# Teensy_3_1_XBee_Adapter.net
KiCad netlist of a schematic drawn in EAGLE
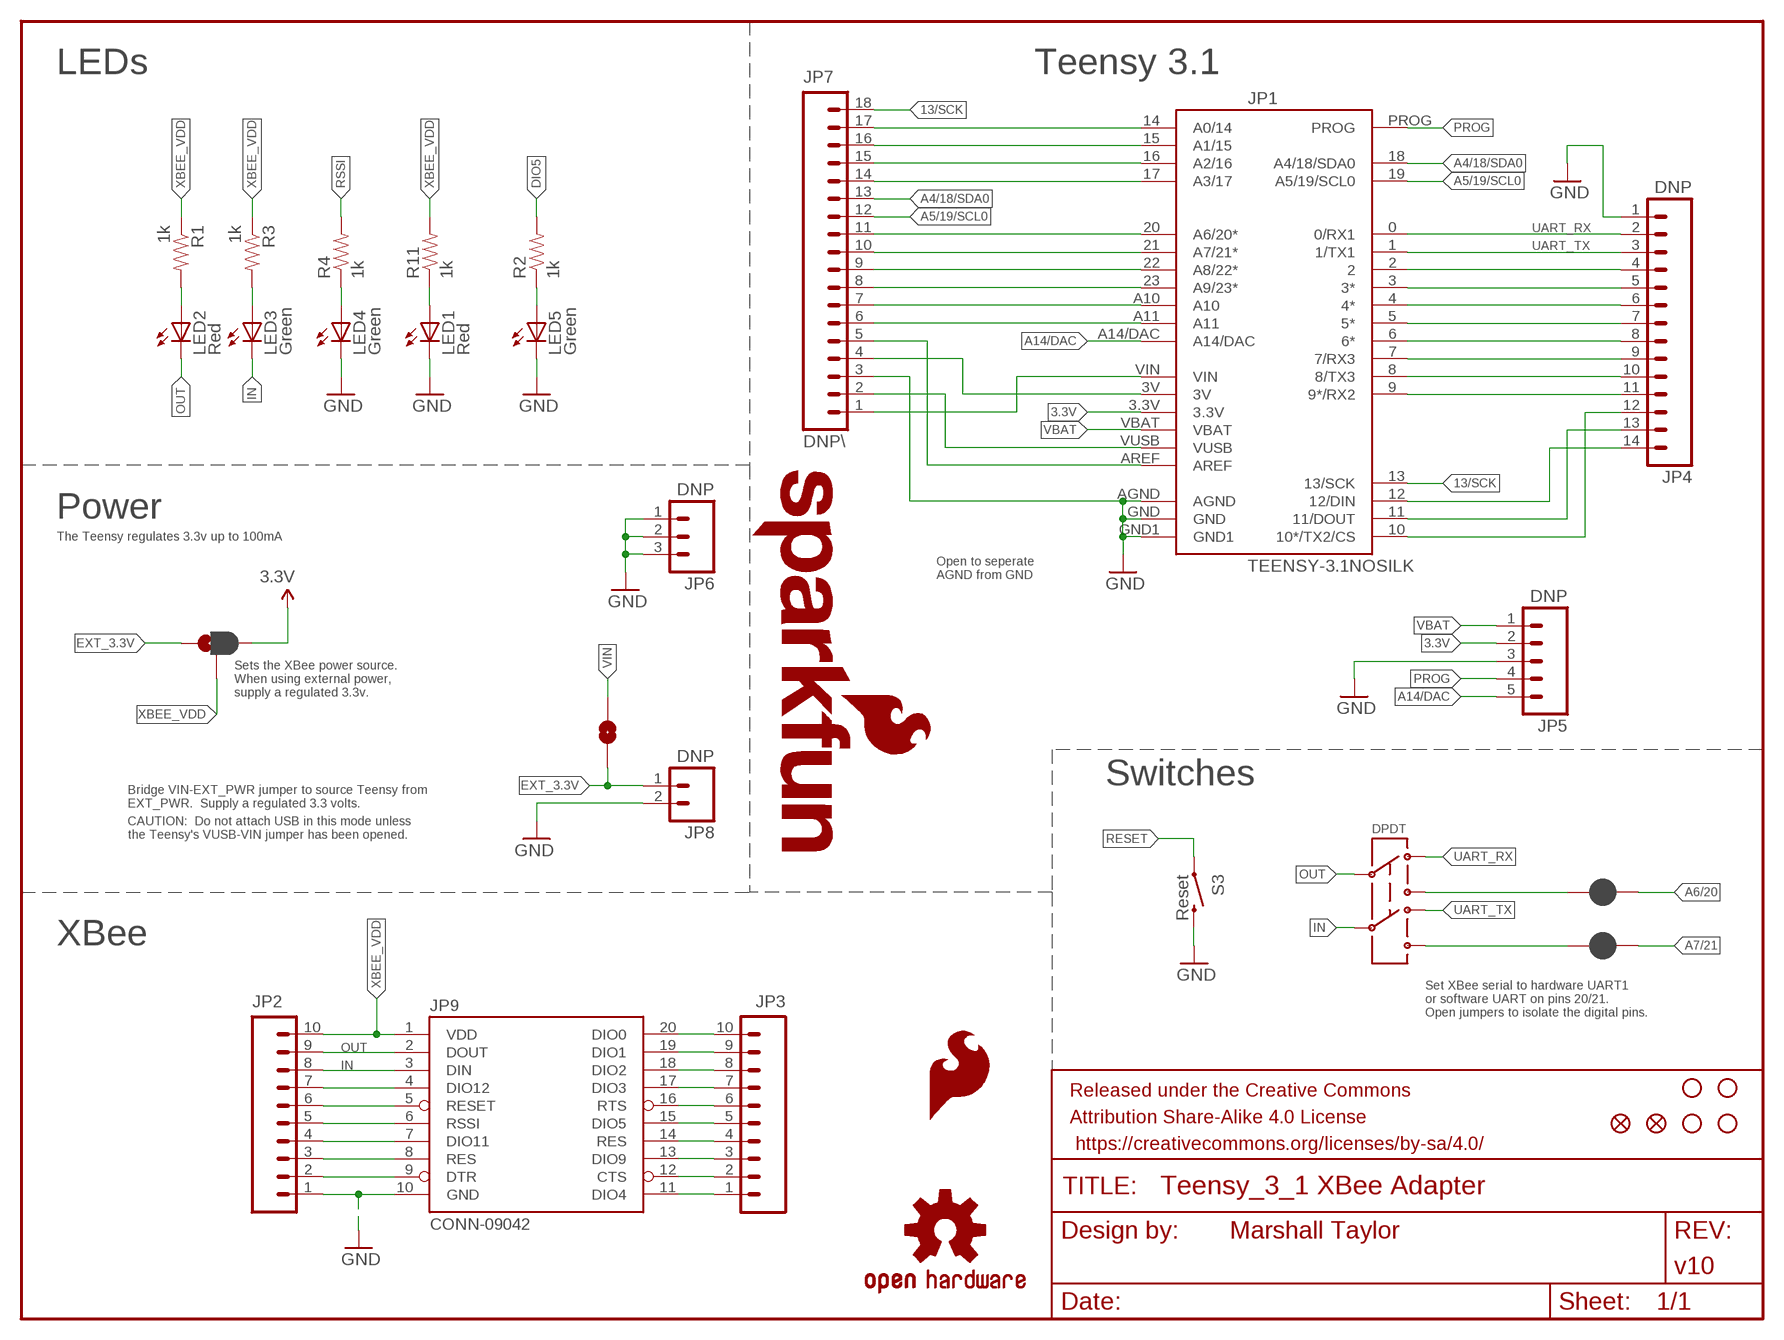
[diagram p0: schematic, sheet 1]

(export (version "E")
  (design (tool "Eeschema 10.0.6"))
  (components
    (comp (ref "FID1")
      (value "FIDUCIAL1X2")
      (footprint "eagle-import:FIDUCIAL-1X2")
      (libsource (lib "eagle-import") (part "FIDUCIAL1X2"))
    )
    (comp (ref "FID2")
      (value "FIDUCIAL1X2")
      (footprint "eagle-import:FIDUCIAL-1X2")
      (libsource (lib "eagle-import") (part "FIDUCIAL1X2"))
    )
    (comp (ref "FRAME1")
      (value "FRAME-LETTER")
      (footprint "eagle-import:CREATIVE_COMMONS")
      (fields
        (field (name "DESIGNER") "Marshall Taylor")
        (field (name "VERSION") "v10")
        (field (name "DESIGNER_1") "Marshall Taylor")
        (field (name "VERSION_1") "v10")
      )
      (libsource (lib "eagle-import") (part "FRAME-LETTER"))
    )
    (comp (ref "JP1")
      (value "TEENSY-3.1NOSILK")
      (footprint "eagle-import:TEENSY-3.1_NOSILK")
      (libsource (lib "eagle-import") (part "TEENSY-3.1NOSILK"))
    )
    (comp (ref "JP2")
      (value "M10NO_SILK_PTH_FEMALE")
      (footprint "eagle-import:1X10_NO_SILK")
      (libsource (lib "eagle-import") (part "M10NO_SILK_PTH_FEMALE"))
    )
    (comp (ref "JP3")
      (value "M10NO_SILK_PTH_FEMALE")
      (footprint "eagle-import:1X10_NO_SILK")
      (libsource (lib "eagle-import") (part "M10NO_SILK_PTH_FEMALE"))
    )
    (comp (ref "JP4")
      (value "DNP")
      (footprint "eagle-import:1X14")
      (libsource (lib "eagle-import") (part "M14"))
    )
    (comp (ref "JP5")
      (value "DNP")
      (footprint "eagle-import:1X05")
      (libsource (lib "eagle-import") (part "M05PTH"))
    )
    (comp (ref "JP6")
      (value "DNP")
      (footprint "eagle-import:1X03")
      (libsource (lib "eagle-import") (part "M03PTH"))
    )
    (comp (ref "JP7")
      (value "DNP\\")
      (footprint "eagle-import:1X18")
      (libsource (lib "eagle-import") (part "M18_"))
    )
    (comp (ref "JP8")
      (value "DNP")
      (footprint "eagle-import:1X02")
      (libsource (lib "eagle-import") (part "M02PTH"))
    )
    (comp (ref "JP9")
      (value "CONN-09042")
      (footprint "eagle-import:XBEE-SMD")
      (libsource (lib "eagle-import") (part "XBEE-1B3"))
    )
    (comp (ref "LED1")
      (value "Red")
      (footprint "eagle-import:LED-0603")
      (libsource (lib "eagle-import") (part "LED-RED0603"))
    )
    (comp (ref "LED2")
      (value "Red")
      (footprint "eagle-import:LED-0603")
      (libsource (lib "eagle-import") (part "LED-RED0603"))
    )
    (comp (ref "LED3")
      (value "Green")
      (footprint "eagle-import:LED-0603")
      (libsource (lib "eagle-import") (part "LED-GREEN0603"))
    )
    (comp (ref "LED4")
      (value "Green")
      (footprint "eagle-import:LED-0603")
      (libsource (lib "eagle-import") (part "LED-GREEN0603"))
    )
    (comp (ref "LED5")
      (value "Green")
      (footprint "eagle-import:LED-0603")
      (libsource (lib "eagle-import") (part "LED-GREEN0603"))
    )
    (comp (ref "LOGO1")
      (value "SFE_LOGO_FLAME.2_INCH")
      (footprint "eagle-import:SFE_LOGO_FLAME_.2")
      (libsource (lib "eagle-import") (part "SFE_LOGO_FLAME.2_INCH"))
    )
    (comp (ref "LOGO2")
      (value "OSHW-LOGOM")
      (footprint "eagle-import:OSHW-LOGO-M")
      (libsource (lib "eagle-import") (part "OSHW-LOGOM"))
    )
    (comp (ref "LOGO3")
      (value "SFE_LOGO_NAME_FLAME.2_INCH")
      (footprint "eagle-import:SFE_LOGO_NAME_FLAME_.2")
      (libsource (lib "eagle-import") (part "SFE_LOGO_NAME_FLAME.2_INCH"))
    )
    (comp (ref "R1")
      (value "1k")
      (footprint "eagle-import:0603-RES")
      (libsource (lib "eagle-import") (part "1KOHM1/10W1%(0603)"))
    )
    (comp (ref "R2")
      (value "1k")
      (footprint "eagle-import:0603-RES")
      (libsource (lib "eagle-import") (part "1KOHM1/10W1%(0603)"))
    )
    (comp (ref "R3")
      (value "1k")
      (footprint "eagle-import:0603-RES")
      (libsource (lib "eagle-import") (part "1KOHM1/10W1%(0603)"))
    )
    (comp (ref "R4")
      (value "1k")
      (footprint "eagle-import:0603-RES")
      (libsource (lib "eagle-import") (part "1KOHM1/10W1%(0603)"))
    )
    (comp (ref "R11")
      (value "1k")
      (footprint "eagle-import:0603-RES")
      (libsource (lib "eagle-import") (part "1KOHM1/10W1%(0603)"))
    )
    (comp (ref "S2")
      (value "DPDT")
      (footprint "eagle-import:AYZ0202")
      (libsource (lib "eagle-import") (part "SWITCH-DPDTAYZ0202"))
    )
    (comp (ref "S3")
      (value "Reset")
      (footprint "eagle-import:TACTILE-SWITCH-SMD")
      (libsource (lib "eagle-import") (part "SWITCH-MOMENTARY-2SMD"))
    )
    (comp (ref "SJ1")
      (value "D_TX")
      (footprint "eagle-import:PAD-JUMPER-2-NC_BY_PASTE_YES_SILK")
      (libsource (lib "eagle-import") (part "JUMPER-PAD-2-NC_BY_PASTE"))
    )
    (comp (ref "SJ3")
      (value "D_RX")
      (footprint "eagle-import:PAD-JUMPER-2-NC_BY_PASTE_YES_SILK")
      (libsource (lib "eagle-import") (part "JUMPER-PAD-2-NC_BY_PASTE"))
    )
    (comp (ref "SJ4")
      (value "JUMPER-PAD-3-2OF3_NC_BY_PASTE")
      (footprint "eagle-import:PAD-JUMPER-3-2OF3_NC_BY_PASTE_YES_SILK_FULL_BOX")
      (libsource (lib "eagle-import") (part "JUMPER-PAD-3-2OF3_NC_BY_PASTE"))
    )
    (comp (ref "SJ5")
      (value "EXT_JPR")
      (footprint "eagle-import:PAD-JUMPER-2-NO_YES_SILK")
      (libsource (lib "eagle-import") (part "JUMPER-PAD-2-NOYES_SILK"))
    )
    (comp (ref "STANDOFF1")
      (value "STAND-OFF")
      (footprint "eagle-import:STAND-OFF")
      (libsource (lib "eagle-import") (part "STAND-OFF"))
    )
    (comp (ref "STANDOFF2")
      (value "STAND-OFF")
      (footprint "eagle-import:STAND-OFF")
      (libsource (lib "eagle-import") (part "STAND-OFF"))
    )
    (comp (ref "STANDOFF3")
      (value "STAND-OFF")
      (footprint "eagle-import:STAND-OFF")
      (libsource (lib "eagle-import") (part "STAND-OFF"))
    )
    (comp (ref "STANDOFF4")
      (value "STAND-OFF")
      (footprint "eagle-import:STAND-OFF")
      (libsource (lib "eagle-import") (part "STAND-OFF"))
    )
  )
  (nets
    (net (code "1") (name "3.3V") (class "Default")
      (node (ref "JP1") (pin "3.3V") (pinfunction "3.3V_3.3V") (pintype "bidirectional"))
      (node (ref "JP5") (pin "2") (pinfunction "2_2") (pintype "passive"))
      (node (ref "SJ4") (pin "3") (pinfunction "3_3") (pintype "passive"))
    )
    (net (code "2") (name "13{slash}SCK") (class "Default")
      (node (ref "JP1") (pin "13") (pinfunction "13/SCK_13") (pintype "bidirectional"))
      (node (ref "JP7") (pin "18") (pinfunction "18_18") (pintype "passive"))
    )
    (net (code "3") (name "A4{slash}18{slash}SDA0") (class "Default")
      (node (ref "JP1") (pin "18") (pinfunction "A4/18/SDA0_18") (pintype "bidirectional"))
      (node (ref "JP7") (pin "13") (pinfunction "13_13") (pintype "passive"))
    )
    (net (code "4") (name "A5{slash}19{slash}SCL0") (class "Default")
      (node (ref "JP1") (pin "19") (pinfunction "A5/19/SCL0_19") (pintype "bidirectional"))
      (node (ref "JP7") (pin "12") (pinfunction "12_12") (pintype "passive"))
    )
    (net (code "5") (name "A6{slash}20") (class "Default")
      (node (ref "JP1") (pin "20") (pinfunction "A6/20*_20") (pintype "bidirectional"))
      (node (ref "JP7") (pin "11") (pinfunction "11_11") (pintype "passive"))
      (node (ref "SJ3") (pin "1") (pinfunction "1_1") (pintype "passive"))
    )
    (net (code "6") (name "A7{slash}21") (class "Default")
      (node (ref "JP1") (pin "21") (pinfunction "A7/21*_21") (pintype "bidirectional"))
      (node (ref "JP7") (pin "10") (pinfunction "10_10") (pintype "passive"))
      (node (ref "SJ1") (pin "1") (pinfunction "1_1") (pintype "passive"))
    )
    (net (code "7") (name "A14{slash}DAC") (class "Default")
      (node (ref "JP1") (pin "A14/DAC") (pinfunction "A14/DAC_A14/DAC") (pintype "bidirectional"))
      (node (ref "JP5") (pin "5") (pinfunction "5_5") (pintype "passive"))
    )
    (net (code "8") (name "DIO5") (class "Default")
      (node (ref "JP3") (pin "5") (pinfunction "5_5") (pintype "passive"))
      (node (ref "JP9") (pin "15") (pinfunction "DIO5_15") (pintype "bidirectional"))
      (node (ref "R2") (pin "2") (pinfunction "2_2") (pintype "passive"))
    )
    (net (code "9") (name "EXT_3.3V") (class "Default")
      (node (ref "JP8") (pin "1") (pinfunction "1_1") (pintype "passive"))
      (node (ref "SJ4") (pin "1") (pinfunction "1_1") (pintype "passive"))
      (node (ref "SJ5") (pin "2") (pinfunction "2_2") (pintype "passive"))
    )
    (net (code "10") (name "GND") (class "Default")
      (node (ref "JP1") (pin "AGND") (pinfunction "AGND_AGND") (pintype "bidirectional"))
      (node (ref "JP1") (pin "GND") (pinfunction "GND_GND") (pintype "bidirectional"))
      (node (ref "JP1") (pin "GND1") (pinfunction "GND1_GND1") (pintype "bidirectional"))
      (node (ref "JP2") (pin "1") (pinfunction "1_1") (pintype "passive"))
      (node (ref "JP4") (pin "1") (pinfunction "1_1") (pintype "passive"))
      (node (ref "JP5") (pin "3") (pinfunction "3_3") (pintype "passive"))
      (node (ref "JP6") (pin "1") (pinfunction "1_1") (pintype "passive"))
      (node (ref "JP6") (pin "2") (pinfunction "2_2") (pintype "passive"))
      (node (ref "JP6") (pin "3") (pinfunction "3_3") (pintype "passive"))
      (node (ref "JP7") (pin "3") (pinfunction "3_3") (pintype "passive"))
      (node (ref "JP8") (pin "2") (pinfunction "2_2") (pintype "passive"))
      (node (ref "JP9") (pin "10") (pinfunction "GND_10") (pintype "power_in"))
      (node (ref "LED1") (pin "C") (pinfunction "C_C") (pintype "passive"))
      (node (ref "LED4") (pin "C") (pinfunction "C_C") (pintype "passive"))
      (node (ref "LED5") (pin "C") (pinfunction "C_C") (pintype "passive"))
      (node (ref "S3") (pin "3") (pinfunction "2_3") (pintype "passive"))
    )
    (net (code "11") (name "IN") (class "Default")
      (node (ref "JP2") (pin "8") (pinfunction "8_8") (pintype "passive"))
      (node (ref "JP9") (pin "3") (pinfunction "DIN_3") (pintype "input"))
      (node (ref "LED3") (pin "C") (pinfunction "C_C") (pintype "passive"))
      (node (ref "S2") (pin "5") (pinfunction "5_5") (pintype "bidirectional"))
    )
    (net (code "12") (name "Net-(JP1-3*)") (class "Default")
      (node (ref "JP1") (pin "3") (pinfunction "3*_3") (pintype "bidirectional"))
      (node (ref "JP4") (pin "5") (pinfunction "5_5") (pintype "passive"))
    )
    (net (code "13") (name "Net-(JP1-4*)") (class "Default")
      (node (ref "JP1") (pin "4") (pinfunction "4*_4") (pintype "bidirectional"))
      (node (ref "JP4") (pin "6") (pinfunction "6_6") (pintype "passive"))
    )
    (net (code "14") (name "Net-(JP1-5*)") (class "Default")
      (node (ref "JP1") (pin "5") (pinfunction "5*_5") (pintype "bidirectional"))
      (node (ref "JP4") (pin "7") (pinfunction "7_7") (pintype "passive"))
    )
    (net (code "15") (name "Net-(JP1-6*)") (class "Default")
      (node (ref "JP1") (pin "6") (pinfunction "6*_6") (pintype "bidirectional"))
      (node (ref "JP4") (pin "8") (pinfunction "8_8") (pintype "passive"))
    )
    (net (code "16") (name "Net-(JP1-7{slash}RX3)") (class "Default")
      (node (ref "JP1") (pin "7") (pinfunction "7/RX3_7") (pintype "bidirectional"))
      (node (ref "JP4") (pin "9") (pinfunction "9_9") (pintype "passive"))
    )
    (net (code "17") (name "Net-(JP1-8{slash}TX3)") (class "Default")
      (node (ref "JP1") (pin "8") (pinfunction "8/TX3_8") (pintype "bidirectional"))
      (node (ref "JP4") (pin "10") (pinfunction "10_10") (pintype "passive"))
    )
    (net (code "18") (name "Net-(JP1-9*{slash}RX2)") (class "Default")
      (node (ref "JP1") (pin "9") (pinfunction "9*/RX2_9") (pintype "bidirectional"))
      (node (ref "JP4") (pin "11") (pinfunction "11_11") (pintype "passive"))
    )
    (net (code "19") (name "Net-(JP1-10*{slash}TX2{slash}CS)") (class "Default")
      (node (ref "JP1") (pin "10") (pinfunction "10*/TX2/CS_10") (pintype "bidirectional"))
      (node (ref "JP4") (pin "12") (pinfunction "12_12") (pintype "passive"))
    )
    (net (code "20") (name "Net-(JP1-11{slash}DOUT)") (class "Default")
      (node (ref "JP1") (pin "11") (pinfunction "11/DOUT_11") (pintype "bidirectional"))
      (node (ref "JP4") (pin "13") (pinfunction "13_13") (pintype "passive"))
    )
    (net (code "21") (name "Net-(JP1-12{slash}DIN)") (class "Default")
      (node (ref "JP1") (pin "12") (pinfunction "12/DIN_12") (pintype "bidirectional"))
      (node (ref "JP4") (pin "14") (pinfunction "14_14") (pintype "passive"))
    )
    (net (code "22") (name "Net-(JP1-A0{slash}14)") (class "Default")
      (node (ref "JP1") (pin "14") (pinfunction "A0/14_14") (pintype "bidirectional"))
      (node (ref "JP7") (pin "17") (pinfunction "17_17") (pintype "passive"))
    )
    (net (code "23") (name "Net-(JP1-A1{slash}15)") (class "Default")
      (node (ref "JP1") (pin "15") (pinfunction "A1/15_15") (pintype "bidirectional"))
      (node (ref "JP7") (pin "16") (pinfunction "16_16") (pintype "passive"))
    )
    (net (code "24") (name "Net-(JP1-A2{slash}16)") (class "Default")
      (node (ref "JP1") (pin "16") (pinfunction "A2/16_16") (pintype "bidirectional"))
      (node (ref "JP7") (pin "15") (pinfunction "15_15") (pintype "passive"))
    )
    (net (code "25") (name "Net-(JP1-A3{slash}17)") (class "Default")
      (node (ref "JP1") (pin "17") (pinfunction "A3/17_17") (pintype "bidirectional"))
      (node (ref "JP7") (pin "14") (pinfunction "14_14") (pintype "passive"))
    )
    (net (code "26") (name "Net-(JP1-A8{slash}22*)") (class "Default")
      (node (ref "JP1") (pin "22") (pinfunction "A8/22*_22") (pintype "bidirectional"))
      (node (ref "JP7") (pin "9") (pinfunction "9_9") (pintype "passive"))
    )
    (net (code "27") (name "Net-(JP1-A9{slash}23*)") (class "Default")
      (node (ref "JP1") (pin "23") (pinfunction "A9/23*_23") (pintype "bidirectional"))
      (node (ref "JP7") (pin "8") (pinfunction "8_8") (pintype "passive"))
    )
    (net (code "28") (name "Net-(JP1-Pad2)") (class "Default")
      (node (ref "JP1") (pin "2") (pinfunction "2_2") (pintype "bidirectional"))
      (node (ref "JP4") (pin "4") (pinfunction "4_4") (pintype "passive"))
    )
    (net (code "29") (name "Net-(JP1-Pad3V)") (class "Default")
      (node (ref "JP1") (pin "3V") (pinfunction "3V_3V") (pintype "bidirectional"))
      (node (ref "JP7") (pin "4") (pinfunction "4_4") (pintype "passive"))
    )
    (net (code "30") (name "Net-(JP1-PadA10)") (class "Default")
      (node (ref "JP1") (pin "A10") (pinfunction "A10_A10") (pintype "bidirectional"))
      (node (ref "JP7") (pin "7") (pinfunction "7_7") (pintype "passive"))
    )
    (net (code "31") (name "Net-(JP1-PadA11)") (class "Default")
      (node (ref "JP1") (pin "A11") (pinfunction "A11_A11") (pintype "bidirectional"))
      (node (ref "JP7") (pin "6") (pinfunction "6_6") (pintype "passive"))
    )
    (net (code "32") (name "Net-(JP1-PadAREF)") (class "Default")
      (node (ref "JP1") (pin "AREF") (pinfunction "AREF_AREF") (pintype "bidirectional"))
      (node (ref "JP7") (pin "5") (pinfunction "5_5") (pintype "passive"))
    )
    (net (code "33") (name "Net-(JP1-PadVUSB)") (class "Default")
      (node (ref "JP1") (pin "VUSB") (pinfunction "VUSB_VUSB") (pintype "bidirectional"))
      (node (ref "JP7") (pin "2") (pinfunction "2_2") (pintype "passive"))
    )
    (net (code "34") (name "Net-(JP2-Pad3)") (class "Default")
      (node (ref "JP2") (pin "3") (pinfunction "3_3") (pintype "passive"))
      (node (ref "JP9") (pin "8") (pinfunction "RES_8") (pintype "bidirectional"))
    )
    (net (code "35") (name "Net-(JP3-Pad4)") (class "Default")
      (node (ref "JP3") (pin "4") (pinfunction "4_4") (pintype "passive"))
      (node (ref "JP9") (pin "14") (pinfunction "RES_14") (pintype "bidirectional"))
    )
    (net (code "36") (name "Net-(JP9-CTS)") (class "Default")
      (node (ref "JP3") (pin "2") (pinfunction "2_2") (pintype "passive"))
      (node (ref "JP9") (pin "12") (pinfunction "CTS_12") (pintype "output"))
    )
    (net (code "37") (name "Net-(JP9-DIO0)") (class "Default")
      (node (ref "JP3") (pin "10") (pinfunction "10_10") (pintype "passive"))
      (node (ref "JP9") (pin "20") (pinfunction "DIO0_20") (pintype "bidirectional"))
    )
    (net (code "38") (name "Net-(JP9-DIO1)") (class "Default")
      (node (ref "JP3") (pin "9") (pinfunction "9_9") (pintype "passive"))
      (node (ref "JP9") (pin "19") (pinfunction "DIO1_19") (pintype "bidirectional"))
    )
    (net (code "39") (name "Net-(JP9-DIO2)") (class "Default")
      (node (ref "JP3") (pin "8") (pinfunction "8_8") (pintype "passive"))
      (node (ref "JP9") (pin "18") (pinfunction "DIO2_18") (pintype "bidirectional"))
    )
    (net (code "40") (name "Net-(JP9-DIO3)") (class "Default")
      (node (ref "JP3") (pin "7") (pinfunction "7_7") (pintype "passive"))
      (node (ref "JP9") (pin "17") (pinfunction "DIO3_17") (pintype "bidirectional"))
    )
    (net (code "41") (name "Net-(JP9-DIO4)") (class "Default")
      (node (ref "JP3") (pin "1") (pinfunction "1_1") (pintype "passive"))
      (node (ref "JP9") (pin "11") (pinfunction "DIO4_11") (pintype "bidirectional"))
    )
    (net (code "42") (name "Net-(JP9-DIO9)") (class "Default")
      (node (ref "JP3") (pin "3") (pinfunction "3_3") (pintype "passive"))
      (node (ref "JP9") (pin "13") (pinfunction "DIO9_13") (pintype "bidirectional"))
    )
    (net (code "43") (name "Net-(JP9-DIO11)") (class "Default")
      (node (ref "JP2") (pin "4") (pinfunction "4_4") (pintype "passive"))
      (node (ref "JP9") (pin "7") (pinfunction "DIO11_7") (pintype "bidirectional"))
    )
    (net (code "44") (name "Net-(JP9-DIO12)") (class "Default")
      (node (ref "JP2") (pin "7") (pinfunction "7_7") (pintype "passive"))
      (node (ref "JP9") (pin "4") (pinfunction "DIO12_4") (pintype "bidirectional"))
    )
    (net (code "45") (name "Net-(JP9-DTR)") (class "Default")
      (node (ref "JP2") (pin "2") (pinfunction "2_2") (pintype "passive"))
      (node (ref "JP9") (pin "9") (pinfunction "DTR_9") (pintype "bidirectional"))
    )
    (net (code "46") (name "Net-(JP9-RTS)") (class "Default")
      (node (ref "JP3") (pin "6") (pinfunction "6_6") (pintype "passive"))
      (node (ref "JP9") (pin "16") (pinfunction "RTS_16") (pintype "input"))
    )
    (net (code "47") (name "Net-(LED1-PadA)") (class "Default")
      (node (ref "LED1") (pin "A") (pinfunction "A_A") (pintype "passive"))
      (node (ref "R11") (pin "1") (pinfunction "1_1") (pintype "passive"))
    )
    (net (code "48") (name "Net-(LED2-PadA)") (class "Default")
      (node (ref "LED2") (pin "A") (pinfunction "A_A") (pintype "passive"))
      (node (ref "R1") (pin "2") (pinfunction "2_2") (pintype "passive"))
    )
    (net (code "49") (name "Net-(LED3-PadA)") (class "Default")
      (node (ref "LED3") (pin "A") (pinfunction "A_A") (pintype "passive"))
      (node (ref "R3") (pin "2") (pinfunction "2_2") (pintype "passive"))
    )
    (net (code "50") (name "Net-(LED4-PadA)") (class "Default")
      (node (ref "LED4") (pin "A") (pinfunction "A_A") (pintype "passive"))
      (node (ref "R4") (pin "1") (pinfunction "1_1") (pintype "passive"))
    )
    (net (code "51") (name "Net-(LED5-PadA)") (class "Default")
      (node (ref "LED5") (pin "A") (pinfunction "A_A") (pintype "passive"))
      (node (ref "R2") (pin "1") (pinfunction "1_1") (pintype "passive"))
    )
    (net (code "52") (name "Net-(S2-Pad3)") (class "Default")
      (node (ref "S2") (pin "3") (pinfunction "3_3") (pintype "bidirectional"))
      (node (ref "SJ3") (pin "2") (pinfunction "2_2") (pintype "passive"))
    )
    (net (code "53") (name "Net-(S2-Pad6)") (class "Default")
      (node (ref "S2") (pin "6") (pinfunction "6_6") (pintype "bidirectional"))
      (node (ref "SJ1") (pin "2") (pinfunction "2_2") (pintype "passive"))
    )
    (net (code "54") (name "OUT") (class "Default")
      (node (ref "JP2") (pin "9") (pinfunction "9_9") (pintype "passive"))
      (node (ref "JP9") (pin "2") (pinfunction "DOUT_2") (pintype "output"))
      (node (ref "LED2") (pin "C") (pinfunction "C_C") (pintype "passive"))
      (node (ref "S2") (pin "2") (pinfunction "2_2") (pintype "bidirectional"))
    )
    (net (code "55") (name "PROG") (class "Default")
      (node (ref "JP1") (pin "PROG") (pinfunction "PROG_PROG") (pintype "bidirectional"))
      (node (ref "JP5") (pin "4") (pinfunction "4_4") (pintype "passive"))
    )
    (net (code "56") (name "RESET") (class "Default")
      (node (ref "JP2") (pin "6") (pinfunction "6_6") (pintype "passive"))
      (node (ref "JP9") (pin "5") (pinfunction "RESET_5") (pintype "input"))
      (node (ref "S3") (pin "1") (pinfunction "1_1") (pintype "passive"))
    )
    (net (code "57") (name "RSSI") (class "Default")
      (node (ref "JP2") (pin "5") (pinfunction "5_5") (pintype "passive"))
      (node (ref "JP9") (pin "6") (pinfunction "RSSI_6") (pintype "bidirectional"))
      (node (ref "R4") (pin "2") (pinfunction "2_2") (pintype "passive"))
    )
    (net (code "58") (name "UART_RX") (class "Default")
      (node (ref "JP1") (pin "0") (pinfunction "0/RX1_0") (pintype "bidirectional"))
      (node (ref "JP4") (pin "2") (pinfunction "2_2") (pintype "passive"))
      (node (ref "S2") (pin "1") (pinfunction "1_1") (pintype "bidirectional"))
    )
    (net (code "59") (name "UART_TX") (class "Default")
      (node (ref "JP1") (pin "1") (pinfunction "1/TX1_1") (pintype "bidirectional"))
      (node (ref "JP4") (pin "3") (pinfunction "3_3") (pintype "passive"))
      (node (ref "S2") (pin "4") (pinfunction "4_4") (pintype "bidirectional"))
    )
    (net (code "60") (name "VBAT") (class "Default")
      (node (ref "JP1") (pin "VBAT") (pinfunction "VBAT_VBAT") (pintype "bidirectional"))
      (node (ref "JP5") (pin "1") (pinfunction "1_1") (pintype "passive"))
    )
    (net (code "61") (name "VIN") (class "Default")
      (node (ref "JP1") (pin "VIN") (pinfunction "VIN_VIN") (pintype "bidirectional"))
      (node (ref "JP7") (pin "1") (pinfunction "1_1") (pintype "passive"))
      (node (ref "SJ5") (pin "1") (pinfunction "1_1") (pintype "passive"))
    )
    (net (code "62") (name "XBEE_VDD") (class "Default")
      (node (ref "JP2") (pin "10") (pinfunction "10_10") (pintype "passive"))
      (node (ref "JP9") (pin "1") (pinfunction "VDD_1") (pintype "power_in"))
      (node (ref "R1") (pin "1") (pinfunction "1_1") (pintype "passive"))
      (node (ref "R11") (pin "2") (pinfunction "2_2") (pintype "passive"))
      (node (ref "R3") (pin "1") (pinfunction "1_1") (pintype "passive"))
      (node (ref "SJ4") (pin "2") (pinfunction "2_2") (pintype "passive"))
    )
  )
)
